# phychipDevelopmentBoardV0_9.net
KiCad netlist of a schematic drawn in EAGLE
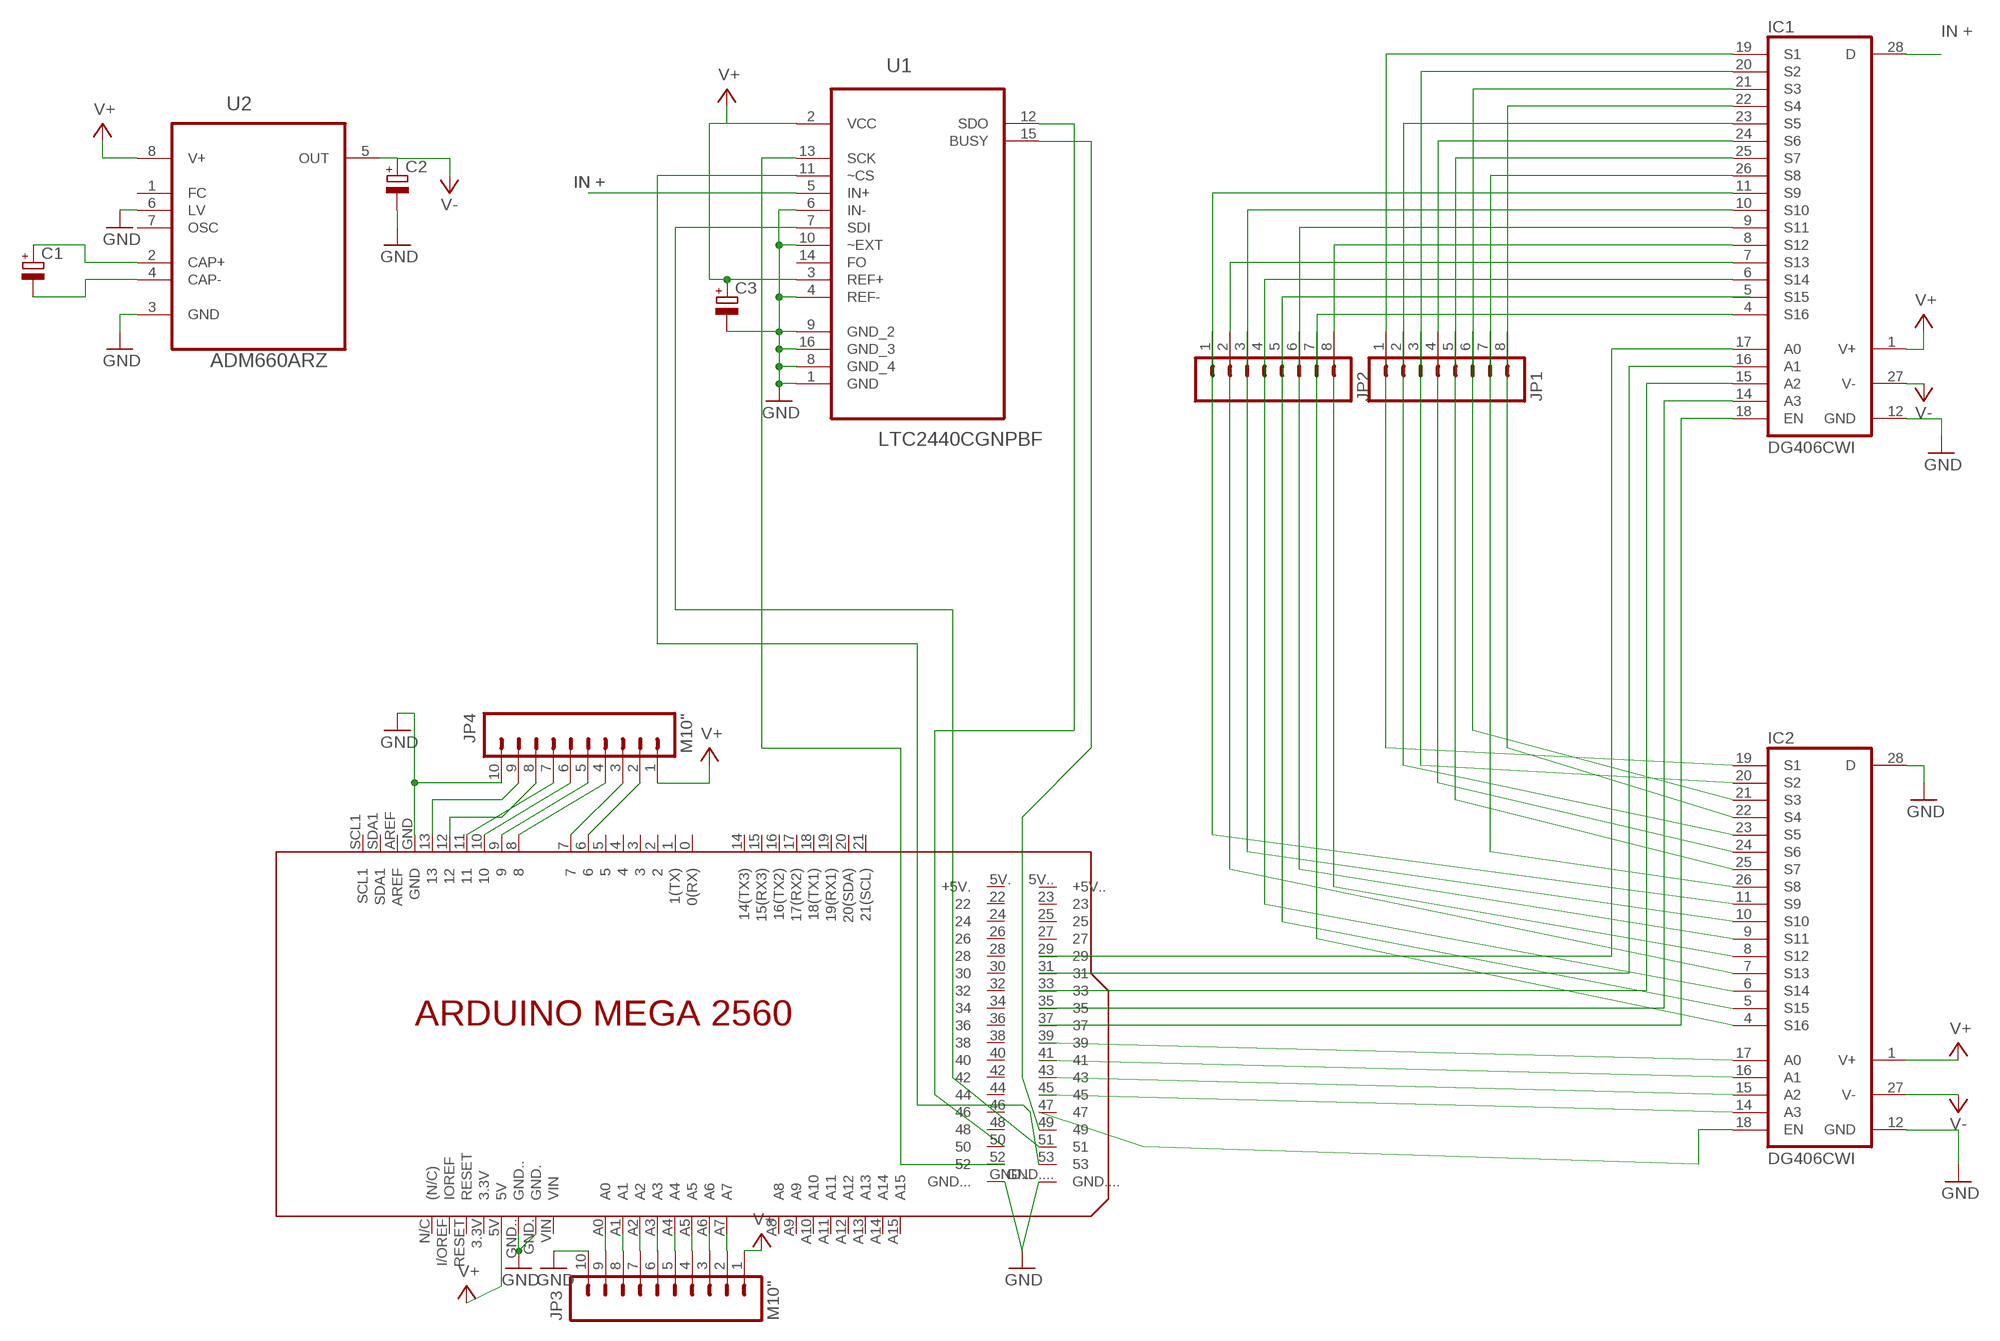
[diagram p0: schematic, sheet 1]

(export (version "E")
  (design (tool "Eeschema 10.0.6"))
  (components
    (comp (ref "C1")
      (value "CPOL-EU153CLV-0505")
      (footprint "eagle-import:153CLV-0505")
      (libsource (lib "eagle-import") (part "CPOL-EU153CLV-0505"))
    )
    (comp (ref "C2")
      (value "CPOL-EU153CLV-0505")
      (footprint "eagle-import:153CLV-0505")
      (libsource (lib "eagle-import") (part "CPOL-EU153CLV-0505"))
    )
    (comp (ref "C3")
      (value "CPOL-EU153CLV-0505")
      (footprint "eagle-import:153CLV-0505")
      (libsource (lib "eagle-import") (part "CPOL-EU153CLV-0505"))
    )
    (comp (ref "IC1")
      (value "DG406CWI")
      (footprint "eagle-import:SO28L")
      (fields (field (name "MF") "MAXIM"))
      (libsource (lib "eagle-import") (part "DG406CWI"))
    )
    (comp (ref "IC2")
      (value "DG406CWI")
      (footprint "eagle-import:SO28L")
      (fields (field (name "MF") "MAXIM"))
      (libsource (lib "eagle-import") (part "DG406CWI"))
    )
    (comp (ref "JP1")
      (value "M08")
      (footprint "eagle-import:1X08")
      (libsource (lib "eagle-import") (part "M08"))
    )
    (comp (ref "JP2")
      (value "M08")
      (footprint "eagle-import:1X08")
      (libsource (lib "eagle-import") (part "M08"))
    )
    (comp (ref "JP3")
      (value "M10\"")
      (footprint "eagle-import:1X10")
      (libsource (lib "eagle-import") (part "M10{dblquote}"))
    )
    (comp (ref "JP4")
      (value "M10\"")
      (footprint "eagle-import:1X10")
      (libsource (lib "eagle-import") (part "M10{dblquote}"))
    )
    (comp (ref "PCB1")
      (value "ARDUINO_MEGA2560")
      (footprint "eagle-import:ARDUINO_MEGA2560")
      (libsource (lib "eagle-import") (part "ARDUINO_MEGA2560"))
    )
    (comp (ref "U1")
      (value "LTC2440CGNPBF")
      (footprint "eagle-import:SOP63P600X175-16N")
      (fields (field (name "MPN") "LTC2440CGN#PBF"))
      (libsource (lib "eagle-import") (part "LTC2440CGNPBF"))
    )
    (comp (ref "U2")
      (value "ADM660ARZ")
      (footprint "eagle-import:SOIC127P600X175-8N")
      (libsource (lib "eagle-import") (part "ADM660ARZ"))
    )
  )
  (nets
    (net (code "1") (name "/IN+") (class "Default")
      (node (ref "IC1") (pin "28") (pinfunction "D_28") (pintype "passive"))
      (node (ref "U1") (pin "5") (pinfunction "IN+_5") (pintype "input"))
    )
    (net (code "2") (name "GND") (class "Default")
      (node (ref "C2") (pin "-") (pinfunction "-_-") (pintype "passive"))
      (node (ref "C3") (pin "-") (pinfunction "-_-") (pintype "passive"))
      (node (ref "IC1") (pin "12") (pinfunction "GND_12") (pintype "power_in"))
      (node (ref "IC2") (pin "12") (pinfunction "GND_12") (pintype "power_in"))
      (node (ref "IC2") (pin "28") (pinfunction "D_28") (pintype "passive"))
      (node (ref "JP3") (pin "10") (pinfunction "10_10") (pintype "passive"))
      (node (ref "JP4") (pin "10") (pinfunction "10_10") (pintype "passive"))
      (node (ref "PCB1") (pin "GND") (pinfunction "GND_GND") (pintype "bidirectional"))
      (node (ref "PCB1") (pin "GND.") (pinfunction "GND._GND.") (pintype "bidirectional"))
      (node (ref "PCB1") (pin "GND..") (pinfunction "GND.._GND..") (pintype "bidirectional"))
      (node (ref "PCB1") (pin "GND...") (pinfunction "GND..._GND...") (pintype "bidirectional"))
      (node (ref "PCB1") (pin "GND....") (pinfunction "GND...._GND....") (pintype "bidirectional"))
      (node (ref "U1") (pin "1") (pinfunction "GND_1") (pintype "passive"))
      (node (ref "U1") (pin "10") (pinfunction "~{EXT}_10") (pintype "input"))
      (node (ref "U1") (pin "16") (pinfunction "GND_3_16") (pintype "passive"))
      (node (ref "U1") (pin "4") (pinfunction "REF-_4") (pintype "input"))
      (node (ref "U1") (pin "6") (pinfunction "IN-_6") (pintype "input"))
      (node (ref "U1") (pin "8") (pinfunction "GND_4_8") (pintype "passive"))
      (node (ref "U1") (pin "9") (pinfunction "GND_2_9") (pintype "passive"))
      (node (ref "U2") (pin "3") (pinfunction "GND_3") (pintype "passive"))
      (node (ref "U2") (pin "6") (pinfunction "LV_6") (pintype "input"))
    )
    (net (code "3") (name "Net-(IC1-A0)") (class "Default")
      (node (ref "IC1") (pin "17") (pinfunction "A0_17") (pintype "input"))
      (node (ref "PCB1") (pin "29") (pinfunction "29_29") (pintype "bidirectional"))
    )
    (net (code "4") (name "Net-(IC1-A1)") (class "Default")
      (node (ref "IC1") (pin "16") (pinfunction "A1_16") (pintype "input"))
      (node (ref "PCB1") (pin "31") (pinfunction "31_31") (pintype "bidirectional"))
    )
    (net (code "5") (name "Net-(IC1-A2)") (class "Default")
      (node (ref "IC1") (pin "15") (pinfunction "A2_15") (pintype "input"))
      (node (ref "PCB1") (pin "33") (pinfunction "33_33") (pintype "bidirectional"))
    )
    (net (code "6") (name "Net-(IC1-A3)") (class "Default")
      (node (ref "IC1") (pin "14") (pinfunction "A3_14") (pintype "input"))
      (node (ref "PCB1") (pin "35") (pinfunction "35_35") (pintype "bidirectional"))
    )
    (net (code "7") (name "Net-(IC1-EN)") (class "Default")
      (node (ref "IC1") (pin "18") (pinfunction "EN_18") (pintype "input"))
      (node (ref "PCB1") (pin "37") (pinfunction "37_37") (pintype "bidirectional"))
    )
    (net (code "8") (name "Net-(IC1-S1)") (class "Default")
      (node (ref "IC1") (pin "19") (pinfunction "S1_19") (pintype "passive"))
      (node (ref "IC2") (pin "19") (pinfunction "S1_19") (pintype "passive"))
      (node (ref "JP1") (pin "1") (pinfunction "1_1") (pintype "passive"))
    )
    (net (code "9") (name "Net-(IC1-S2)") (class "Default")
      (node (ref "IC1") (pin "20") (pinfunction "S2_20") (pintype "passive"))
      (node (ref "IC2") (pin "20") (pinfunction "S2_20") (pintype "passive"))
      (node (ref "JP1") (pin "3") (pinfunction "3_3") (pintype "passive"))
    )
    (net (code "10") (name "Net-(IC1-S3)") (class "Default")
      (node (ref "IC1") (pin "21") (pinfunction "S3_21") (pintype "passive"))
      (node (ref "IC2") (pin "21") (pinfunction "S3_21") (pintype "passive"))
      (node (ref "JP1") (pin "6") (pinfunction "6_6") (pintype "passive"))
    )
    (net (code "11") (name "Net-(IC1-S4)") (class "Default")
      (node (ref "IC1") (pin "22") (pinfunction "S4_22") (pintype "passive"))
      (node (ref "IC2") (pin "22") (pinfunction "S4_22") (pintype "passive"))
      (node (ref "JP1") (pin "8") (pinfunction "8_8") (pintype "passive"))
    )
    (net (code "12") (name "Net-(IC1-S5)") (class "Default")
      (node (ref "IC1") (pin "23") (pinfunction "S5_23") (pintype "passive"))
      (node (ref "IC2") (pin "23") (pinfunction "S5_23") (pintype "passive"))
      (node (ref "JP1") (pin "2") (pinfunction "2_2") (pintype "passive"))
    )
    (net (code "13") (name "Net-(IC1-S6)") (class "Default")
      (node (ref "IC1") (pin "24") (pinfunction "S6_24") (pintype "passive"))
      (node (ref "IC2") (pin "24") (pinfunction "S6_24") (pintype "passive"))
      (node (ref "JP1") (pin "4") (pinfunction "4_4") (pintype "passive"))
    )
    (net (code "14") (name "Net-(IC1-S7)") (class "Default")
      (node (ref "IC1") (pin "25") (pinfunction "S7_25") (pintype "passive"))
      (node (ref "IC2") (pin "25") (pinfunction "S7_25") (pintype "passive"))
      (node (ref "JP1") (pin "5") (pinfunction "5_5") (pintype "passive"))
    )
    (net (code "15") (name "Net-(IC1-S8)") (class "Default")
      (node (ref "IC1") (pin "26") (pinfunction "S8_26") (pintype "passive"))
      (node (ref "IC2") (pin "26") (pinfunction "S8_26") (pintype "passive"))
      (node (ref "JP1") (pin "7") (pinfunction "7_7") (pintype "passive"))
    )
    (net (code "16") (name "Net-(IC1-S9)") (class "Default")
      (node (ref "IC1") (pin "11") (pinfunction "S9_11") (pintype "passive"))
      (node (ref "IC2") (pin "11") (pinfunction "S9_11") (pintype "passive"))
      (node (ref "JP2") (pin "1") (pinfunction "1_1") (pintype "passive"))
    )
    (net (code "17") (name "Net-(IC1-S10)") (class "Default")
      (node (ref "IC1") (pin "10") (pinfunction "S10_10") (pintype "passive"))
      (node (ref "IC2") (pin "10") (pinfunction "S10_10") (pintype "passive"))
      (node (ref "JP2") (pin "3") (pinfunction "3_3") (pintype "passive"))
    )
    (net (code "18") (name "Net-(IC1-S11)") (class "Default")
      (node (ref "IC1") (pin "9") (pinfunction "S11_9") (pintype "passive"))
      (node (ref "IC2") (pin "9") (pinfunction "S11_9") (pintype "passive"))
      (node (ref "JP2") (pin "6") (pinfunction "6_6") (pintype "passive"))
    )
    (net (code "19") (name "Net-(IC1-S12)") (class "Default")
      (node (ref "IC1") (pin "8") (pinfunction "S12_8") (pintype "passive"))
      (node (ref "IC2") (pin "8") (pinfunction "S12_8") (pintype "passive"))
      (node (ref "JP2") (pin "8") (pinfunction "8_8") (pintype "passive"))
    )
    (net (code "20") (name "Net-(IC1-S13)") (class "Default")
      (node (ref "IC1") (pin "7") (pinfunction "S13_7") (pintype "passive"))
      (node (ref "IC2") (pin "7") (pinfunction "S13_7") (pintype "passive"))
      (node (ref "JP2") (pin "2") (pinfunction "2_2") (pintype "passive"))
    )
    (net (code "21") (name "Net-(IC1-S14)") (class "Default")
      (node (ref "IC1") (pin "6") (pinfunction "S14_6") (pintype "passive"))
      (node (ref "IC2") (pin "6") (pinfunction "S14_6") (pintype "passive"))
      (node (ref "JP2") (pin "4") (pinfunction "4_4") (pintype "passive"))
    )
    (net (code "22") (name "Net-(IC1-S16)") (class "Default")
      (node (ref "IC1") (pin "4") (pinfunction "S16_4") (pintype "passive"))
      (node (ref "IC2") (pin "4") (pinfunction "S16_4") (pintype "passive"))
      (node (ref "JP2") (pin "7") (pinfunction "7_7") (pintype "passive"))
    )
    (net (code "23") (name "Net-(IC2-A0)") (class "Default")
      (node (ref "IC2") (pin "17") (pinfunction "A0_17") (pintype "input"))
      (node (ref "PCB1") (pin "39") (pinfunction "39_39") (pintype "bidirectional"))
    )
    (net (code "24") (name "Net-(IC2-A1)") (class "Default")
      (node (ref "IC2") (pin "16") (pinfunction "A1_16") (pintype "input"))
      (node (ref "PCB1") (pin "41") (pinfunction "41_41") (pintype "bidirectional"))
    )
    (net (code "25") (name "Net-(IC2-A2)") (class "Default")
      (node (ref "IC2") (pin "15") (pinfunction "A2_15") (pintype "input"))
      (node (ref "PCB1") (pin "43") (pinfunction "43_43") (pintype "bidirectional"))
    )
    (net (code "26") (name "Net-(IC2-A3)") (class "Default")
      (node (ref "IC2") (pin "14") (pinfunction "A3_14") (pintype "input"))
      (node (ref "PCB1") (pin "45") (pinfunction "45_45") (pintype "bidirectional"))
    )
    (net (code "27") (name "Net-(IC2-EN)") (class "Default")
      (node (ref "IC2") (pin "18") (pinfunction "EN_18") (pintype "input"))
      (node (ref "PCB1") (pin "47") (pinfunction "47_47") (pintype "bidirectional"))
    )
    (net (code "28") (name "Net-(IC2-S15)") (class "Default")
      (node (ref "IC2") (pin "5") (pinfunction "S15_5") (pintype "passive"))
      (node (ref "JP2") (pin "5") (pinfunction "5_5") (pintype "passive"))
    )
    (net (code "29") (name "Net-(JP3-Pad2)") (class "Default")
      (node (ref "JP3") (pin "2") (pinfunction "2_2") (pintype "passive"))
      (node (ref "PCB1") (pin "A7") (pinfunction "A7_A7") (pintype "bidirectional"))
    )
    (net (code "30") (name "Net-(JP3-Pad3)") (class "Default")
      (node (ref "JP3") (pin "3") (pinfunction "3_3") (pintype "passive"))
      (node (ref "PCB1") (pin "A6") (pinfunction "A6_A6") (pintype "bidirectional"))
    )
    (net (code "31") (name "Net-(JP3-Pad4)") (class "Default")
      (node (ref "JP3") (pin "4") (pinfunction "4_4") (pintype "passive"))
      (node (ref "PCB1") (pin "A5") (pinfunction "A5_A5") (pintype "bidirectional"))
    )
    (net (code "32") (name "Net-(JP3-Pad5)") (class "Default")
      (node (ref "JP3") (pin "5") (pinfunction "5_5") (pintype "passive"))
      (node (ref "PCB1") (pin "A4") (pinfunction "A4_A4") (pintype "bidirectional"))
    )
    (net (code "33") (name "Net-(JP3-Pad6)") (class "Default")
      (node (ref "JP3") (pin "6") (pinfunction "6_6") (pintype "passive"))
      (node (ref "PCB1") (pin "A3") (pinfunction "A3_A3") (pintype "bidirectional"))
    )
    (net (code "34") (name "Net-(JP3-Pad7)") (class "Default")
      (node (ref "JP3") (pin "7") (pinfunction "7_7") (pintype "passive"))
      (node (ref "PCB1") (pin "A2") (pinfunction "A2_A2") (pintype "bidirectional"))
    )
    (net (code "35") (name "Net-(JP3-Pad8)") (class "Default")
      (node (ref "JP3") (pin "8") (pinfunction "8_8") (pintype "passive"))
      (node (ref "PCB1") (pin "A1") (pinfunction "A1_A1") (pintype "bidirectional"))
    )
    (net (code "36") (name "Net-(JP3-Pad9)") (class "Default")
      (node (ref "JP3") (pin "9") (pinfunction "9_9") (pintype "passive"))
      (node (ref "PCB1") (pin "A0") (pinfunction "A0_A0") (pintype "bidirectional"))
    )
    (net (code "37") (name "Net-(JP4-Pad2)") (class "Default")
      (node (ref "JP4") (pin "2") (pinfunction "2_2") (pintype "passive"))
      (node (ref "PCB1") (pin "6") (pinfunction "6_6") (pintype "bidirectional"))
    )
    (net (code "38") (name "Net-(JP4-Pad3)") (class "Default")
      (node (ref "JP4") (pin "3") (pinfunction "3_3") (pintype "passive"))
      (node (ref "PCB1") (pin "7") (pinfunction "7_7") (pintype "bidirectional"))
    )
    (net (code "39") (name "Net-(JP4-Pad4)") (class "Default")
      (node (ref "JP4") (pin "4") (pinfunction "4_4") (pintype "passive"))
      (node (ref "PCB1") (pin "8") (pinfunction "8_8") (pintype "bidirectional"))
    )
    (net (code "40") (name "Net-(JP4-Pad5)") (class "Default")
      (node (ref "JP4") (pin "5") (pinfunction "5_5") (pintype "passive"))
      (node (ref "PCB1") (pin "9") (pinfunction "9_9") (pintype "bidirectional"))
    )
    (net (code "41") (name "Net-(JP4-Pad6)") (class "Default")
      (node (ref "JP4") (pin "6") (pinfunction "6_6") (pintype "passive"))
      (node (ref "PCB1") (pin "10") (pinfunction "10_10") (pintype "bidirectional"))
    )
    (net (code "42") (name "Net-(JP4-Pad7)") (class "Default")
      (node (ref "JP4") (pin "7") (pinfunction "7_7") (pintype "passive"))
      (node (ref "PCB1") (pin "11") (pinfunction "11_11") (pintype "bidirectional"))
    )
    (net (code "43") (name "Net-(JP4-Pad8)") (class "Default")
      (node (ref "JP4") (pin "8") (pinfunction "8_8") (pintype "passive"))
      (node (ref "PCB1") (pin "12") (pinfunction "12_12") (pintype "bidirectional"))
    )
    (net (code "44") (name "Net-(JP4-Pad9)") (class "Default")
      (node (ref "JP4") (pin "9") (pinfunction "9_9") (pintype "passive"))
      (node (ref "PCB1") (pin "13") (pinfunction "13_13") (pintype "bidirectional"))
    )
    (net (code "45") (name "Net-(U1-BUSY)") (class "Default")
      (node (ref "PCB1") (pin "49") (pinfunction "49_49") (pintype "bidirectional"))
      (node (ref "U1") (pin "15") (pinfunction "BUSY_15") (pintype "output"))
    )
    (net (code "46") (name "Net-(U1-SCK)") (class "Default")
      (node (ref "PCB1") (pin "52") (pinfunction "52_52") (pintype "bidirectional"))
      (node (ref "U1") (pin "13") (pinfunction "SCK_13") (pintype "input"))
    )
    (net (code "47") (name "Net-(U1-SDI)") (class "Default")
      (node (ref "PCB1") (pin "51") (pinfunction "51_51") (pintype "bidirectional"))
      (node (ref "U1") (pin "7") (pinfunction "SDI_7") (pintype "input"))
    )
    (net (code "48") (name "Net-(U1-SDO)") (class "Default")
      (node (ref "PCB1") (pin "50") (pinfunction "50_50") (pintype "bidirectional"))
      (node (ref "U1") (pin "12") (pinfunction "SDO_12") (pintype "output"))
    )
    (net (code "49") (name "Net-(U1-~{CS})") (class "Default")
      (node (ref "PCB1") (pin "53") (pinfunction "53_53") (pintype "bidirectional"))
      (node (ref "U1") (pin "11") (pinfunction "~{CS}_11") (pintype "input"))
    )
    (net (code "50") (name "Net-(U2-CAP+)") (class "Default")
      (node (ref "C1") (pin "+") (pinfunction "+_+") (pintype "passive"))
      (node (ref "U2") (pin "2") (pinfunction "CAP+_2") (pintype "input"))
    )
    (net (code "51") (name "Net-(U2-CAP-)") (class "Default")
      (node (ref "C1") (pin "-") (pinfunction "-_-") (pintype "passive"))
      (node (ref "U2") (pin "4") (pinfunction "CAP-_4") (pintype "input"))
    )
    (net (code "52") (name "V+") (class "Default")
      (node (ref "C3") (pin "+") (pinfunction "+_+") (pintype "passive"))
      (node (ref "IC1") (pin "1") (pinfunction "V+_1") (pintype "power_in"))
      (node (ref "IC2") (pin "1") (pinfunction "V+_1") (pintype "power_in"))
      (node (ref "JP3") (pin "1") (pinfunction "1_1") (pintype "passive"))
      (node (ref "JP4") (pin "1") (pinfunction "1_1") (pintype "passive"))
      (node (ref "PCB1") (pin "5V") (pinfunction "5V_5V") (pintype "bidirectional"))
      (node (ref "U1") (pin "2") (pinfunction "VCC_2") (pintype "power_in"))
      (node (ref "U1") (pin "3") (pinfunction "REF+_3") (pintype "input"))
      (node (ref "U2") (pin "8") (pinfunction "V+_8") (pintype "power_in"))
    )
    (net (code "53") (name "V-") (class "Default")
      (node (ref "C2") (pin "+") (pinfunction "+_+") (pintype "passive"))
      (node (ref "IC1") (pin "27") (pinfunction "V-_27") (pintype "power_in"))
      (node (ref "IC2") (pin "27") (pinfunction "V-_27") (pintype "power_in"))
      (node (ref "U2") (pin "5") (pinfunction "OUT_5") (pintype "output"))
    )
    (net (code "54") (name "unconnected-(IC1-S15-Pad5)") (class "Default")
      (node (ref "IC1") (pin "5") (pinfunction "S15_5") (pintype "passive"))
    )
    (net (code "55") (name "unconnected-(PCB1-(N{slash}C)-PadN{slash}C)") (class "Default")
      (node (ref "PCB1") (pin "N/C") (pinfunction "(N/C)_N/C") (pintype "bidirectional"))
    )
    (net (code "56") (name "unconnected-(PCB1-+5V.-Pad5V.)") (class "Default")
      (node (ref "PCB1") (pin "5V.") (pinfunction "+5V._5V.") (pintype "bidirectional"))
    )
    (net (code "57") (name "unconnected-(PCB1-+5V..-Pad5V..)") (class "Default")
      (node (ref "PCB1") (pin "5V..") (pinfunction "+5V.._5V..") (pintype "bidirectional"))
    )
    (net (code "58") (name "unconnected-(PCB1-0(RX)-Pad0)") (class "Default")
      (node (ref "PCB1") (pin "0") (pinfunction "0(RX)_0") (pintype "bidirectional"))
    )
    (net (code "59") (name "unconnected-(PCB1-1(TX)-Pad1)") (class "Default")
      (node (ref "PCB1") (pin "1") (pinfunction "1(TX)_1") (pintype "bidirectional"))
    )
    (net (code "60") (name "unconnected-(PCB1-14(TX3)-Pad14)") (class "Default")
      (node (ref "PCB1") (pin "14") (pinfunction "14(TX3)_14") (pintype "bidirectional"))
    )
    (net (code "61") (name "unconnected-(PCB1-15(RX3)-Pad15)") (class "Default")
      (node (ref "PCB1") (pin "15") (pinfunction "15(RX3)_15") (pintype "bidirectional"))
    )
    (net (code "62") (name "unconnected-(PCB1-16(TX2)-Pad16)") (class "Default")
      (node (ref "PCB1") (pin "16") (pinfunction "16(TX2)_16") (pintype "bidirectional"))
    )
    (net (code "63") (name "unconnected-(PCB1-17(RX2)-Pad17)") (class "Default")
      (node (ref "PCB1") (pin "17") (pinfunction "17(RX2)_17") (pintype "bidirectional"))
    )
    (net (code "64") (name "unconnected-(PCB1-18(TX1)-Pad18)") (class "Default")
      (node (ref "PCB1") (pin "18") (pinfunction "18(TX1)_18") (pintype "bidirectional"))
    )
    (net (code "65") (name "unconnected-(PCB1-19(RX1)-Pad19)") (class "Default")
      (node (ref "PCB1") (pin "19") (pinfunction "19(RX1)_19") (pintype "bidirectional"))
    )
    (net (code "66") (name "unconnected-(PCB1-20(SDA)-Pad20)") (class "Default")
      (node (ref "PCB1") (pin "20") (pinfunction "20(SDA)_20") (pintype "bidirectional"))
    )
    (net (code "67") (name "unconnected-(PCB1-21(SCL)-Pad21)") (class "Default")
      (node (ref "PCB1") (pin "21") (pinfunction "21(SCL)_21") (pintype "bidirectional"))
    )
    (net (code "68") (name "unconnected-(PCB1-IOREF-PadI{slash}OREF)") (class "Default")
      (node (ref "PCB1") (pin "I/OREF") (pinfunction "IOREF_I/OREF") (pintype "bidirectional"))
    )
    (net (code "69") (name "unconnected-(PCB1-Pad2)") (class "Default")
      (node (ref "PCB1") (pin "2") (pinfunction "2_2") (pintype "bidirectional"))
    )
    (net (code "70") (name "unconnected-(PCB1-Pad3)") (class "Default")
      (node (ref "PCB1") (pin "3") (pinfunction "3_3") (pintype "bidirectional"))
    )
    (net (code "71") (name "unconnected-(PCB1-Pad3.3V)") (class "Default")
      (node (ref "PCB1") (pin "3.3V") (pinfunction "3.3V_3.3V") (pintype "bidirectional"))
    )
    (net (code "72") (name "unconnected-(PCB1-Pad4)") (class "Default")
      (node (ref "PCB1") (pin "4") (pinfunction "4_4") (pintype "bidirectional"))
    )
    (net (code "73") (name "unconnected-(PCB1-Pad5)") (class "Default")
      (node (ref "PCB1") (pin "5") (pinfunction "5_5") (pintype "bidirectional"))
    )
    (net (code "74") (name "unconnected-(PCB1-Pad22)") (class "Default")
      (node (ref "PCB1") (pin "22") (pinfunction "22_22") (pintype "bidirectional"))
    )
    (net (code "75") (name "unconnected-(PCB1-Pad23)") (class "Default")
      (node (ref "PCB1") (pin "23") (pinfunction "23_23") (pintype "bidirectional"))
    )
    (net (code "76") (name "unconnected-(PCB1-Pad24)") (class "Default")
      (node (ref "PCB1") (pin "24") (pinfunction "24_24") (pintype "bidirectional"))
    )
    (net (code "77") (name "unconnected-(PCB1-Pad25)") (class "Default")
      (node (ref "PCB1") (pin "25") (pinfunction "25_25") (pintype "bidirectional"))
    )
    (net (code "78") (name "unconnected-(PCB1-Pad26)") (class "Default")
      (node (ref "PCB1") (pin "26") (pinfunction "26_26") (pintype "bidirectional"))
    )
    (net (code "79") (name "unconnected-(PCB1-Pad27)") (class "Default")
      (node (ref "PCB1") (pin "27") (pinfunction "27_27") (pintype "bidirectional"))
    )
    (net (code "80") (name "unconnected-(PCB1-Pad28)") (class "Default")
      (node (ref "PCB1") (pin "28") (pinfunction "28_28") (pintype "bidirectional"))
    )
    (net (code "81") (name "unconnected-(PCB1-Pad30)") (class "Default")
      (node (ref "PCB1") (pin "30") (pinfunction "30_30") (pintype "bidirectional"))
    )
    (net (code "82") (name "unconnected-(PCB1-Pad32)") (class "Default")
      (node (ref "PCB1") (pin "32") (pinfunction "32_32") (pintype "bidirectional"))
    )
    (net (code "83") (name "unconnected-(PCB1-Pad34)") (class "Default")
      (node (ref "PCB1") (pin "34") (pinfunction "34_34") (pintype "bidirectional"))
    )
    (net (code "84") (name "unconnected-(PCB1-Pad36)") (class "Default")
      (node (ref "PCB1") (pin "36") (pinfunction "36_36") (pintype "bidirectional"))
    )
    (net (code "85") (name "unconnected-(PCB1-Pad38)") (class "Default")
      (node (ref "PCB1") (pin "38") (pinfunction "38_38") (pintype "bidirectional"))
    )
    (net (code "86") (name "unconnected-(PCB1-Pad40)") (class "Default")
      (node (ref "PCB1") (pin "40") (pinfunction "40_40") (pintype "bidirectional"))
    )
    (net (code "87") (name "unconnected-(PCB1-Pad42)") (class "Default")
      (node (ref "PCB1") (pin "42") (pinfunction "42_42") (pintype "bidirectional"))
    )
    (net (code "88") (name "unconnected-(PCB1-Pad44)") (class "Default")
      (node (ref "PCB1") (pin "44") (pinfunction "44_44") (pintype "bidirectional"))
    )
    (net (code "89") (name "unconnected-(PCB1-Pad46)") (class "Default")
      (node (ref "PCB1") (pin "46") (pinfunction "46_46") (pintype "bidirectional"))
    )
    (net (code "90") (name "unconnected-(PCB1-Pad48)") (class "Default")
      (node (ref "PCB1") (pin "48") (pinfunction "48_48") (pintype "bidirectional"))
    )
    (net (code "91") (name "unconnected-(PCB1-PadA8)") (class "Default")
      (node (ref "PCB1") (pin "A8") (pinfunction "A8_A8") (pintype "bidirectional"))
    )
    (net (code "92") (name "unconnected-(PCB1-PadA9)") (class "Default")
      (node (ref "PCB1") (pin "A9") (pinfunction "A9_A9") (pintype "bidirectional"))
    )
    (net (code "93") (name "unconnected-(PCB1-PadA10)") (class "Default")
      (node (ref "PCB1") (pin "A10") (pinfunction "A10_A10") (pintype "bidirectional"))
    )
    (net (code "94") (name "unconnected-(PCB1-PadA11)") (class "Default")
      (node (ref "PCB1") (pin "A11") (pinfunction "A11_A11") (pintype "bidirectional"))
    )
    (net (code "95") (name "unconnected-(PCB1-PadA12)") (class "Default")
      (node (ref "PCB1") (pin "A12") (pinfunction "A12_A12") (pintype "bidirectional"))
    )
    (net (code "96") (name "unconnected-(PCB1-PadA13)") (class "Default")
      (node (ref "PCB1") (pin "A13") (pinfunction "A13_A13") (pintype "bidirectional"))
    )
    (net (code "97") (name "unconnected-(PCB1-PadA14)") (class "Default")
      (node (ref "PCB1") (pin "A14") (pinfunction "A14_A14") (pintype "bidirectional"))
    )
    (net (code "98") (name "unconnected-(PCB1-PadA15)") (class "Default")
      (node (ref "PCB1") (pin "A15") (pinfunction "A15_A15") (pintype "bidirectional"))
    )
    (net (code "99") (name "unconnected-(PCB1-PadAREF)") (class "Default")
      (node (ref "PCB1") (pin "AREF") (pinfunction "AREF_AREF") (pintype "bidirectional"))
    )
    (net (code "100") (name "unconnected-(PCB1-PadRESET)") (class "Default")
      (node (ref "PCB1") (pin "RESET") (pinfunction "RESET_RESET") (pintype "bidirectional"))
    )
    (net (code "101") (name "unconnected-(PCB1-PadSCL1)") (class "Default")
      (node (ref "PCB1") (pin "SCL1") (pinfunction "SCL1_SCL1") (pintype "bidirectional"))
    )
    (net (code "102") (name "unconnected-(PCB1-PadSDA1)") (class "Default")
      (node (ref "PCB1") (pin "SDA1") (pinfunction "SDA1_SDA1") (pintype "bidirectional"))
    )
    (net (code "103") (name "unconnected-(PCB1-PadVIN)") (class "Default")
      (node (ref "PCB1") (pin "VIN") (pinfunction "VIN_VIN") (pintype "bidirectional"))
    )
    (net (code "104") (name "unconnected-(U1-FO-Pad14)") (class "Default")
      (node (ref "U1") (pin "14") (pinfunction "FO_14") (pintype "input"))
    )
    (net (code "105") (name "unconnected-(U2-FC-Pad1)") (class "Default")
      (node (ref "U2") (pin "1") (pinfunction "FC_1") (pintype "input"))
    )
    (net (code "106") (name "unconnected-(U2-OSC-Pad7)") (class "Default")
      (node (ref "U2") (pin "7") (pinfunction "OSC_7") (pintype "input"))
    )
  )
)
